# Main.net
KiCad netlist of a schematic drawn in Altium Designer
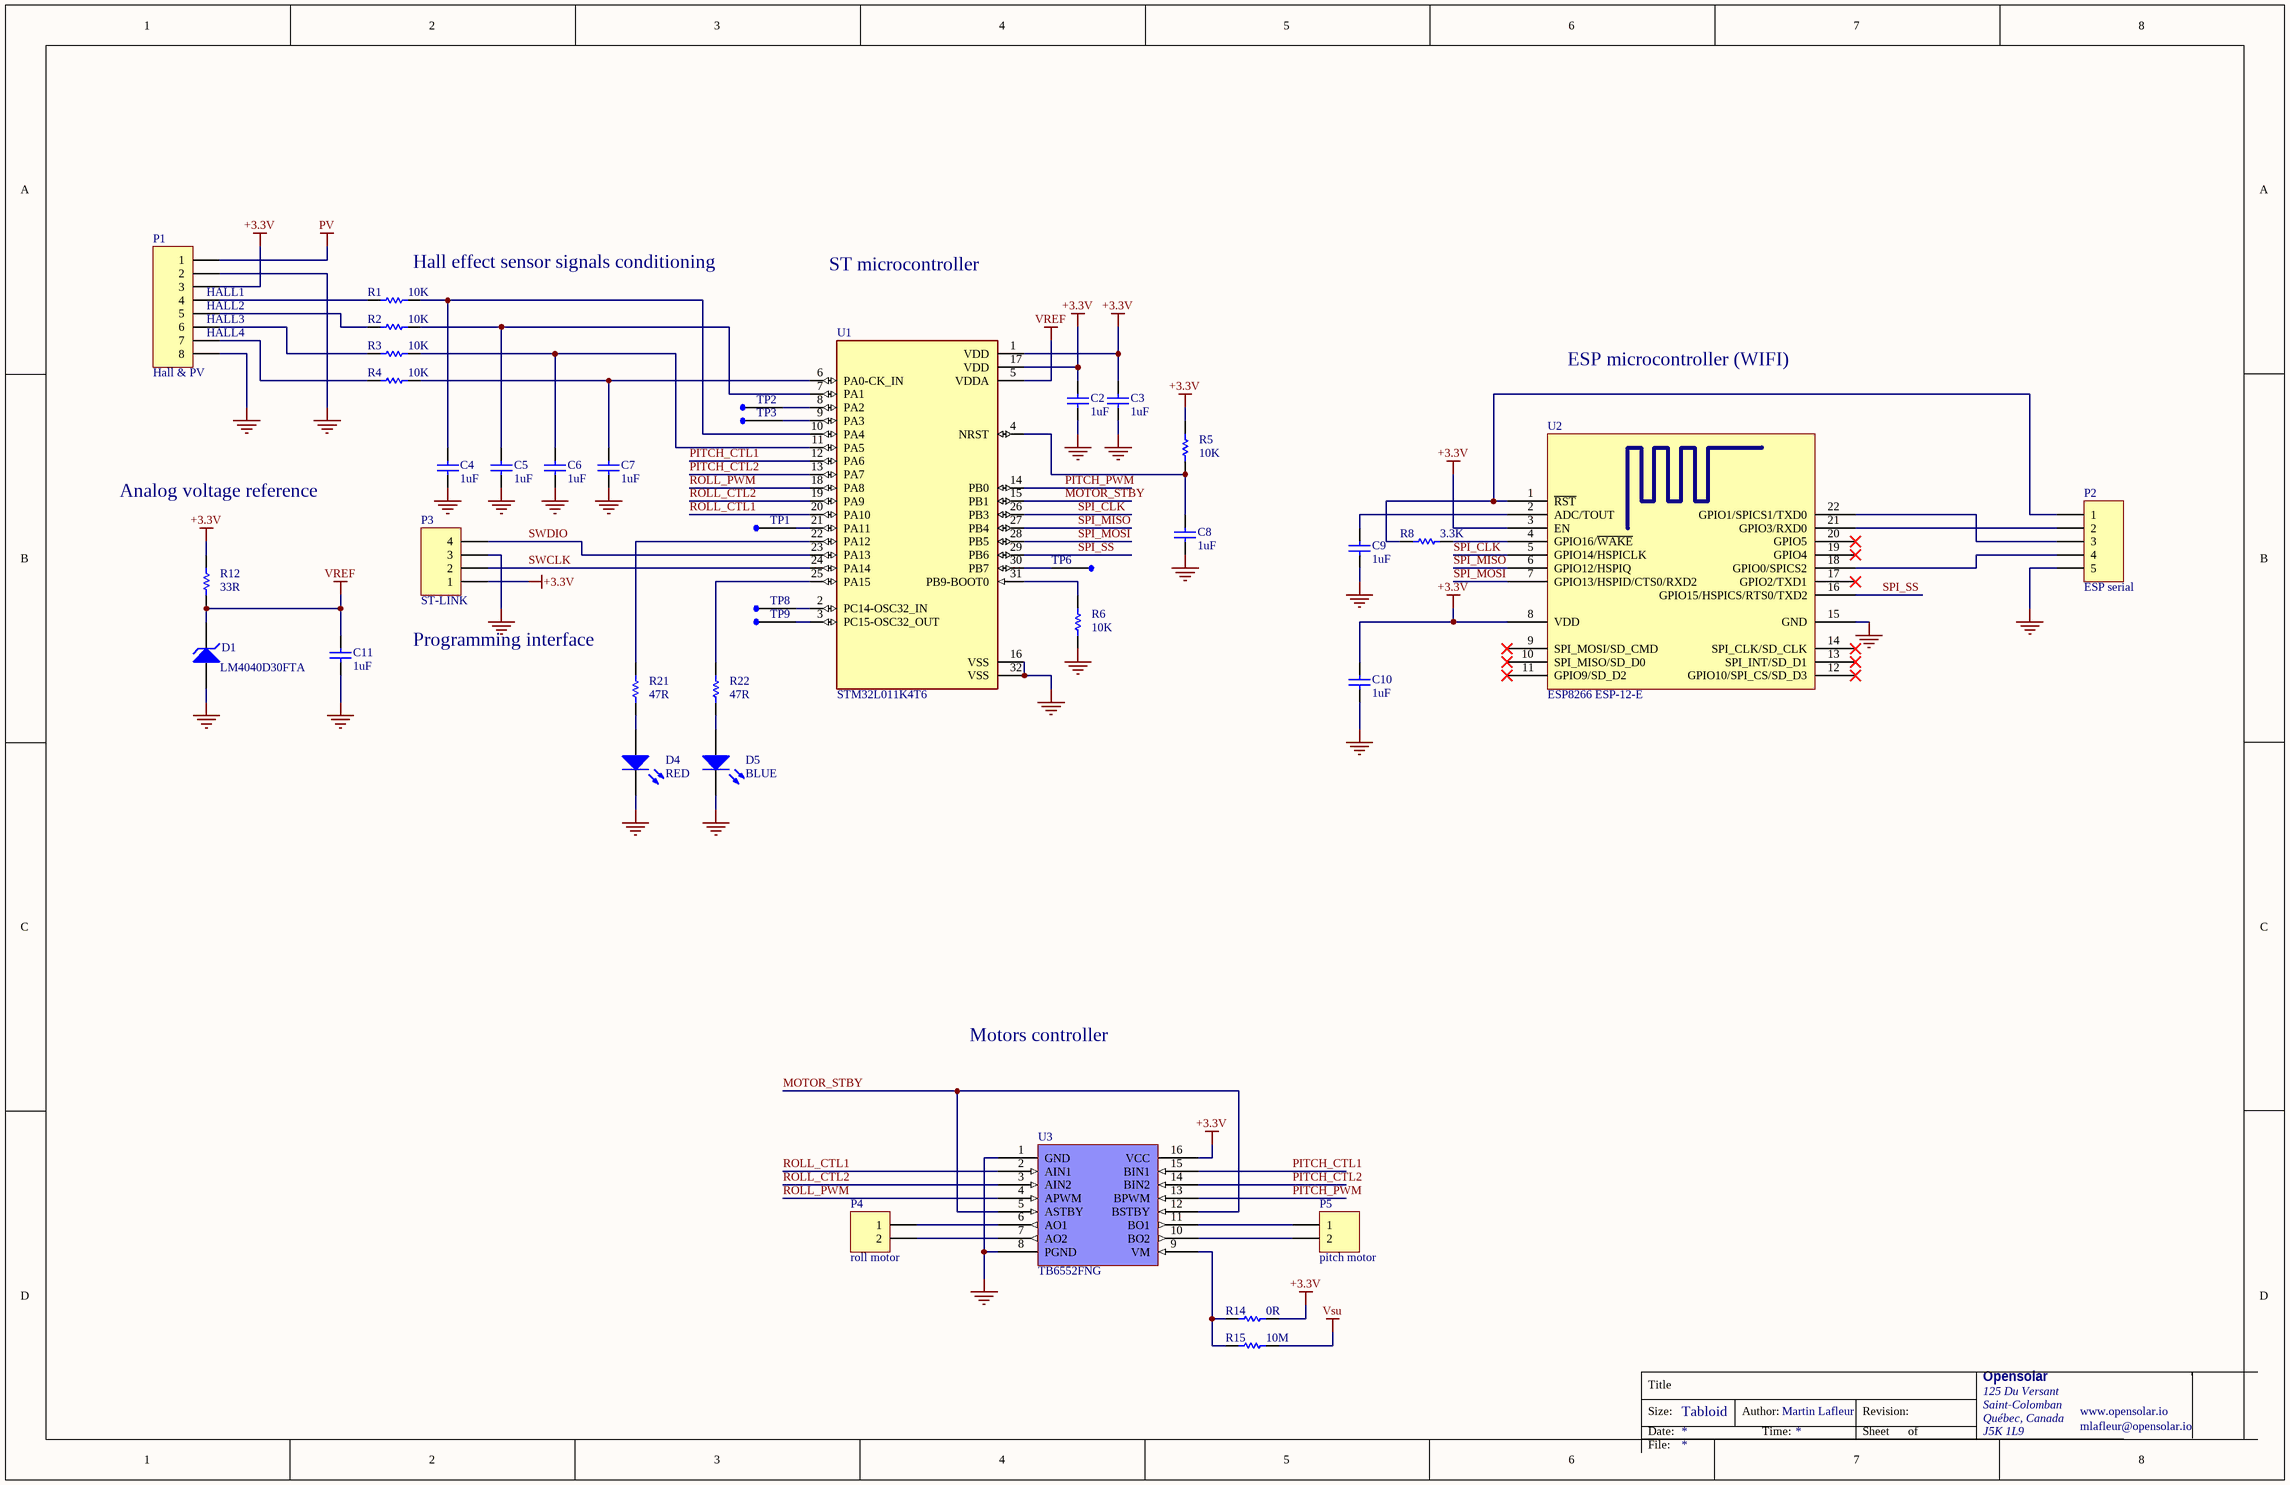
[diagram p0: Main.SchDoc]

(export (version "E")
  (design (tool "Eeschema 10.0.6"))
  (components
    (comp (ref "C2")
      (value "1uF")
      (footprint "6-0805_M")
      (description "Capacitor")
      (fields (field (name "PUBLISHER") "Altium Limited"))
      (libsource (lib "Miscellaneous Devices") (part "Cap"))
    )
    (comp (ref "C3")
      (value "1uF")
      (footprint "6-0805_M")
      (description "Capacitor")
      (fields (field (name "PUBLISHER") "Altium Limited"))
      (libsource (lib "Miscellaneous Devices") (part "Cap"))
    )
    (comp (ref "C4")
      (value "1uF")
      (footprint "6-0805_M")
      (description "Capacitor")
      (fields (field (name "PUBLISHER") "Altium Limited"))
      (libsource (lib "Miscellaneous Devices") (part "Cap"))
    )
    (comp (ref "C5")
      (value "1uF")
      (footprint "6-0805_M")
      (description "Capacitor")
      (fields (field (name "PUBLISHER") "Altium Limited"))
      (libsource (lib "Miscellaneous Devices") (part "Cap"))
    )
    (comp (ref "C6")
      (value "1uF")
      (footprint "6-0805_M")
      (description "Capacitor")
      (fields (field (name "PUBLISHER") "Altium Limited"))
      (libsource (lib "Miscellaneous Devices") (part "Cap"))
    )
    (comp (ref "C7")
      (value "1uF")
      (footprint "6-0805_M")
      (description "Capacitor")
      (fields (field (name "PUBLISHER") "Altium Limited"))
      (libsource (lib "Miscellaneous Devices") (part "Cap"))
    )
    (comp (ref "C8")
      (value "1uF")
      (footprint "6-0805_M")
      (description "Capacitor")
      (fields (field (name "PUBLISHER") "Altium Limited"))
      (libsource (lib "Miscellaneous Devices") (part "Cap"))
    )
    (comp (ref "C9")
      (value "1uF")
      (footprint "6-0805_M")
      (description "Capacitor")
      (fields (field (name "PUBLISHER") "Altium Limited"))
      (libsource (lib "Miscellaneous Devices") (part "Cap"))
    )
    (comp (ref "C10")
      (value "1uF")
      (footprint "6-0805_M")
      (description "Capacitor")
      (fields (field (name "PUBLISHER") "Altium Limited"))
      (libsource (lib "Miscellaneous Devices") (part "Cap"))
    )
    (comp (ref "C11")
      (value "1uF")
      (footprint "6-0805_M")
      (description "Capacitor")
      (fields (field (name "PUBLISHER") "Altium Limited"))
      (libsource (lib "Miscellaneous Devices") (part "Cap"))
    )
    (comp (ref "D1")
      (value "LM4040D30FTA")
      (footprint "SOT23_LM4040")
      (description "Zener Diode")
      (fields (field (name "PUBLISHER") "Altium Limited"))
      (libsource (lib "Miscellaneous Devices") (part "D Zener"))
    )
    (comp (ref "D4")
      (value "RED")
      (footprint "6-0805_M")
      (description "Typical RED, GREEN, YELLOW, AMBER GaAs LED")
      (fields (field (name "PUBLISHER") "Altium Limited"))
      (libsource (lib "Miscellaneous Devices") (part "LED2"))
    )
    (comp (ref "D5")
      (value "BLUE")
      (footprint "6-0805_M")
      (description "Typical RED, GREEN, YELLOW, AMBER GaAs LED")
      (fields (field (name "PUBLISHER") "Altium Limited"))
      (libsource (lib "Miscellaneous Devices") (part "LED2"))
    )
    (comp (ref "P1")
      (value "Hall & PV")
      (footprint "FFC_8")
      (description "Header, 8-Pin")
      (fields (field (name "PUBLISHER") "Altium Limited"))
      (libsource (lib "Miscellaneous Connectors") (part "Header 8"))
    )
    (comp (ref "P2")
      (value "ESP serial")
      (footprint "HEADER-1X5")
      (description "Header, 5-Pin")
      (fields (field (name "PUBLISHER") "Altium Limited"))
      (libsource (lib "Miscellaneous Connectors") (part "Header 5"))
    )
    (comp (ref "P3")
      (value "ST-LINK")
      (footprint "HEADER-1X4")
      (description "Header, 4-Pin")
      (fields (field (name "PUBLISHER") "Altium Limited"))
      (libsource (lib "Miscellaneous Connectors") (part "Header 4"))
    )
    (comp (ref "P4")
      (value "roll motor")
      (footprint "HEADER-1X2")
      (description "Header, 2-Pin")
      (fields (field (name "PUBLISHER") "Altium Limited"))
      (libsource (lib "Miscellaneous Connectors") (part "Header 2"))
    )
    (comp (ref "P5")
      (value "pitch motor")
      (footprint "HEADER-1X2")
      (description "Header, 2-Pin")
      (fields (field (name "PUBLISHER") "Altium Limited"))
      (libsource (lib "") (part "Header 2_1"))
    )
    (comp (ref "R1")
      (value "10K")
      (footprint "6-0805_N")
      (description "Resistor")
      (fields (field (name "PUBLISHER") "Altium Limited"))
      (libsource (lib "Miscellaneous Devices") (part "Res1"))
    )
    (comp (ref "R2")
      (value "10K")
      (footprint "6-0805_N")
      (description "Resistor")
      (fields (field (name "PUBLISHER") "Altium Limited"))
      (libsource (lib "Miscellaneous Devices") (part "Res1"))
    )
    (comp (ref "R3")
      (value "10K")
      (footprint "6-0805_N")
      (description "Resistor")
      (fields (field (name "PUBLISHER") "Altium Limited"))
      (libsource (lib "Miscellaneous Devices") (part "Res1"))
    )
    (comp (ref "R4")
      (value "10K")
      (footprint "6-0805_N")
      (description "Resistor")
      (fields (field (name "PUBLISHER") "Altium Limited"))
      (libsource (lib "Miscellaneous Devices") (part "Res1"))
    )
    (comp (ref "R5")
      (value "10K")
      (footprint "6-0805_N")
      (description "Resistor")
      (fields (field (name "PUBLISHER") "Altium Limited"))
      (libsource (lib "Miscellaneous Devices") (part "Res1"))
    )
    (comp (ref "R6")
      (value "10K")
      (footprint "6-0805_N")
      (description "Resistor")
      (fields (field (name "PUBLISHER") "Altium Limited"))
      (libsource (lib "Miscellaneous Devices") (part "Res1"))
    )
    (comp (ref "R8")
      (value "3.3K")
      (footprint "6-0805_N")
      (description "Resistor")
      (fields (field (name "PUBLISHER") "Altium Limited"))
      (libsource (lib "Miscellaneous Devices") (part "Res1"))
    )
    (comp (ref "R12")
      (value "33R")
      (footprint "6-0805_N")
      (description "Resistor")
      (fields (field (name "PUBLISHER") "Altium Limited"))
      (libsource (lib "Miscellaneous Devices") (part "Res1"))
    )
    (comp (ref "R14")
      (value "0R")
      (footprint "6-0805_N")
      (description "Resistor")
      (fields (field (name "PUBLISHER") "Altium Limited"))
      (libsource (lib "Miscellaneous Devices") (part "Res1"))
    )
    (comp (ref "R15")
      (value "10M")
      (footprint "6-0805_N")
      (description "Resistor")
      (fields (field (name "PUBLISHER") "Altium Limited"))
      (libsource (lib "Miscellaneous Devices") (part "Res1"))
    )
    (comp (ref "R21")
      (value "47R")
      (footprint "6-0805_N")
      (description "Resistor")
      (fields (field (name "PUBLISHER") "Altium Limited"))
      (libsource (lib "Miscellaneous Devices") (part "Res1"))
    )
    (comp (ref "R22")
      (value "47R")
      (footprint "6-0805_N")
      (description "Resistor")
      (fields (field (name "PUBLISHER") "Altium Limited"))
      (libsource (lib "Miscellaneous Devices") (part "Res1"))
    )
    (comp (ref "TP1")
      (value "TEST_POINT")
      (footprint "TEST_POINT_PAD")
      (libsource (lib "laf") (part "TEST_POINT"))
    )
    (comp (ref "TP2")
      (value "TEST_POINT")
      (footprint "TEST_POINT_PAD")
      (libsource (lib "laf") (part "TEST_POINT"))
    )
    (comp (ref "TP3")
      (value "TEST_POINT")
      (footprint "TEST_POINT_PAD")
      (libsource (lib "laf") (part "TEST_POINT"))
    )
    (comp (ref "TP6")
      (value "TEST_POINT")
      (footprint "TEST_POINT_PAD")
      (libsource (lib "laf") (part "TEST_POINT"))
    )
    (comp (ref "TP8")
      (value "TEST_POINT")
      (footprint "TEST_POINT_PAD")
      (libsource (lib "laf") (part "TEST_POINT"))
    )
    (comp (ref "TP9")
      (value "TEST_POINT")
      (footprint "TEST_POINT_PAD")
      (libsource (lib "laf") (part "TEST_POINT"))
    )
    (comp (ref "U1")
      (value "STM32L011K4T6")
      (footprint "QFP80P900X900X160-32N")
      (description "ARMÂ® CortexÂ®-M0 + STM32L0 Microcontrolador IC de 32 bits 32MHz 16KB _16K x 8_ FLASH 32-LQFP _7x7_")
      (fields (field (name "MF") "STMicroelectronics"))
      (libsource (lib "STM32L011K4T6") (part "STM32L011K4T6"))
    )
    (comp (ref "U2")
      (value "ESP8266 ESP-12-E")
      (footprint "ESP8266 ESP-12-E")
      (libsource (lib "ESP8266") (part "ESP8266 ESP-12-E"))
    )
    (comp (ref "U3")
      (value "TB6552FNG")
      (footprint "SSOP16_TB6652")
      (libsource (lib "laf") (part "TB6652PNG"))
    )
  )
  (nets
    (net (code "1") (name "+3.3V") (class "Default")
      (node (ref "C10") (pin "2") (pinfunction "2_2") (pintype "passive"))
      (node (ref "C2") (pin "2") (pinfunction "2_2") (pintype "passive"))
      (node (ref "C3") (pin "2") (pinfunction "2_2") (pintype "passive"))
      (node (ref "P1") (pin "3") (pinfunction "3_3") (pintype "passive"))
      (node (ref "P3") (pin "1") (pinfunction "1_1") (pintype "passive"))
      (node (ref "R12") (pin "2") (pinfunction "2_2") (pintype "passive"))
      (node (ref "R14") (pin "2") (pinfunction "2_2") (pintype "passive"))
      (node (ref "R5") (pin "1") (pinfunction "1_1") (pintype "passive"))
      (node (ref "U1") (pin "1") (pinfunction "VDD_1") (pintype "power_in"))
      (node (ref "U1") (pin "17") (pinfunction "VDD_17") (pintype "power_in"))
      (node (ref "U2") (pin "3") (pinfunction "EN_3") (pintype "passive"))
      (node (ref "U2") (pin "8") (pinfunction "VDD_8") (pintype "passive"))
      (node (ref "U3") (pin "16") (pinfunction "VCC_16") (pintype "power_in"))
    )
    (net (code "2") (name "/MOTOR_STBY") (class "Default")
      (node (ref "U1") (pin "15") (pinfunction "PB1_15") (pintype "bidirectional"))
      (node (ref "U3") (pin "12") (pinfunction "BSTBY_12") (pintype "input"))
      (node (ref "U3") (pin "5") (pinfunction "ASTBY_5") (pintype "input"))
    )
    (net (code "3") (name "/PITCH_CTL1") (class "Default")
      (node (ref "U1") (pin "12") (pinfunction "PA6_12") (pintype "bidirectional"))
      (node (ref "U3") (pin "15") (pinfunction "BIN1_15") (pintype "input"))
    )
    (net (code "4") (name "/PITCH_CTL2") (class "Default")
      (node (ref "U1") (pin "13") (pinfunction "PA7_13") (pintype "bidirectional"))
      (node (ref "U3") (pin "14") (pinfunction "BIN2_14") (pintype "input"))
    )
    (net (code "5") (name "/PITCH_PWM") (class "Default")
      (node (ref "U1") (pin "14") (pinfunction "PB0_14") (pintype "bidirectional"))
      (node (ref "U3") (pin "13") (pinfunction "BPWM_13") (pintype "input"))
    )
    (net (code "6") (name "/ROLL_CTL1") (class "Default")
      (node (ref "U1") (pin "20") (pinfunction "PA10_20") (pintype "bidirectional"))
      (node (ref "U3") (pin "2") (pinfunction "AIN1_2") (pintype "input"))
    )
    (net (code "7") (name "/ROLL_CTL2") (class "Default")
      (node (ref "U1") (pin "19") (pinfunction "PA9_19") (pintype "bidirectional"))
      (node (ref "U3") (pin "3") (pinfunction "AIN2_3") (pintype "input"))
    )
    (net (code "8") (name "/ROLL_PWM") (class "Default")
      (node (ref "U1") (pin "18") (pinfunction "PA8_18") (pintype "bidirectional"))
      (node (ref "U3") (pin "4") (pinfunction "APWM_4") (pintype "input"))
    )
    (net (code "9") (name "/SPI_CLK") (class "Default")
      (node (ref "U1") (pin "26") (pinfunction "PB3_26") (pintype "bidirectional"))
      (node (ref "U2") (pin "5") (pinfunction "GPIO14/HSPICLK_5") (pintype "passive"))
    )
    (net (code "10") (name "/SPI_MISO") (class "Default")
      (node (ref "U1") (pin "27") (pinfunction "PB4_27") (pintype "bidirectional"))
      (node (ref "U2") (pin "6") (pinfunction "GPIO12/HSPIQ_6") (pintype "passive"))
    )
    (net (code "11") (name "/SPI_MOSI") (class "Default")
      (node (ref "U1") (pin "28") (pinfunction "PB5_28") (pintype "bidirectional"))
      (node (ref "U2") (pin "7") (pinfunction "GPIO13/HSPID/CTS0/RXD2_7") (pintype "passive"))
    )
    (net (code "12") (name "/SPI_SS") (class "Default")
      (node (ref "U1") (pin "29") (pinfunction "PB6_29") (pintype "bidirectional"))
      (node (ref "U2") (pin "16") (pinfunction "GPIO15/HSPICS/RTS0/TXD2_16") (pintype "passive"))
    )
    (net (code "13") (name "/SWCLK") (class "Default")
      (node (ref "P3") (pin "2") (pinfunction "2_2") (pintype "passive"))
      (node (ref "U1") (pin "24") (pinfunction "PA14_24") (pintype "bidirectional"))
    )
    (net (code "14") (name "/SWDIO") (class "Default")
      (node (ref "P3") (pin "4") (pinfunction "4_4") (pintype "passive"))
      (node (ref "U1") (pin "23") (pinfunction "PA13_23") (pintype "bidirectional"))
    )
    (net (code "15") (name "GND") (class "Default")
      (node (ref "C10") (pin "1") (pinfunction "1_1") (pintype "passive"))
      (node (ref "C11") (pin "1") (pinfunction "1_1") (pintype "passive"))
      (node (ref "C2") (pin "1") (pinfunction "1_1") (pintype "passive"))
      (node (ref "C3") (pin "1") (pinfunction "1_1") (pintype "passive"))
      (node (ref "C4") (pin "1") (pinfunction "1_1") (pintype "passive"))
      (node (ref "C5") (pin "1") (pinfunction "1_1") (pintype "passive"))
      (node (ref "C6") (pin "1") (pinfunction "1_1") (pintype "passive"))
      (node (ref "C7") (pin "1") (pinfunction "1_1") (pintype "passive"))
      (node (ref "C8") (pin "1") (pinfunction "1_1") (pintype "passive"))
      (node (ref "C9") (pin "1") (pinfunction "1_1") (pintype "passive"))
      (node (ref "D1") (pin "1") (pinfunction "A_1") (pintype "passive"))
      (node (ref "D4") (pin "2") (pinfunction "K_2") (pintype "passive"))
      (node (ref "D5") (pin "2") (pinfunction "K_2") (pintype "passive"))
      (node (ref "P1") (pin "2") (pinfunction "2_2") (pintype "passive"))
      (node (ref "P1") (pin "8") (pinfunction "8_8") (pintype "passive"))
      (node (ref "P2") (pin "5") (pinfunction "5_5") (pintype "passive"))
      (node (ref "P3") (pin "3") (pinfunction "3_3") (pintype "passive"))
      (node (ref "R6") (pin "1") (pinfunction "1_1") (pintype "passive"))
      (node (ref "U1") (pin "16") (pinfunction "VSS_16") (pintype "power_in"))
      (node (ref "U1") (pin "32") (pinfunction "VSS_32") (pintype "power_in"))
      (node (ref "U2") (pin "15") (pinfunction "GND_15") (pintype "passive"))
      (node (ref "U3") (pin "1") (pinfunction "GND_1") (pintype "power_in"))
      (node (ref "U3") (pin "8") (pinfunction "PGND_8") (pintype "power_in"))
    )
    (net (code "16") (name "Net-(D4-A)") (class "Default")
      (node (ref "D4") (pin "1") (pinfunction "A_1") (pintype "passive"))
      (node (ref "R21") (pin "1") (pinfunction "1_1") (pintype "passive"))
    )
    (net (code "17") (name "Net-(D5-A)") (class "Default")
      (node (ref "D5") (pin "1") (pinfunction "A_1") (pintype "passive"))
      (node (ref "R22") (pin "1") (pinfunction "1_1") (pintype "passive"))
    )
    (net (code "18") (name "Net-(P1-Pad4)") (class "Default")
      (node (ref "P1") (pin "4") (pinfunction "4_4") (pintype "passive"))
      (node (ref "R1") (pin "2") (pinfunction "2_2") (pintype "passive"))
    )
    (net (code "19") (name "Net-(P1-Pad5)") (class "Default")
      (node (ref "P1") (pin "5") (pinfunction "5_5") (pintype "passive"))
      (node (ref "R2") (pin "2") (pinfunction "2_2") (pintype "passive"))
    )
    (net (code "20") (name "Net-(P1-Pad6)") (class "Default")
      (node (ref "P1") (pin "6") (pinfunction "6_6") (pintype "passive"))
      (node (ref "R3") (pin "2") (pinfunction "2_2") (pintype "passive"))
    )
    (net (code "21") (name "Net-(P1-Pad7)") (class "Default")
      (node (ref "P1") (pin "7") (pinfunction "7_7") (pintype "passive"))
      (node (ref "R4") (pin "2") (pinfunction "2_2") (pintype "passive"))
    )
    (net (code "22") (name "Net-(TP1-0)") (class "Default")
      (node (ref "TP1") (pin "1") (pinfunction "0_1") (pintype "passive"))
      (node (ref "U1") (pin "21") (pinfunction "PA11_21") (pintype "bidirectional"))
    )
    (net (code "23") (name "Net-(TP2-0)") (class "Default")
      (node (ref "TP2") (pin "1") (pinfunction "0_1") (pintype "passive"))
      (node (ref "U1") (pin "8") (pinfunction "PA2_8") (pintype "bidirectional"))
    )
    (net (code "24") (name "Net-(TP3-0)") (class "Default")
      (node (ref "TP3") (pin "1") (pinfunction "0_1") (pintype "passive"))
      (node (ref "U1") (pin "9") (pinfunction "PA3_9") (pintype "bidirectional"))
    )
    (net (code "25") (name "Net-(TP6-0)") (class "Default")
      (node (ref "TP6") (pin "1") (pinfunction "0_1") (pintype "passive"))
      (node (ref "U1") (pin "30") (pinfunction "PB7_30") (pintype "bidirectional"))
    )
    (net (code "26") (name "Net-(TP8-0)") (class "Default")
      (node (ref "TP8") (pin "1") (pinfunction "0_1") (pintype "passive"))
      (node (ref "U1") (pin "2") (pinfunction "PC14-OSC32_IN_2") (pintype "bidirectional"))
    )
    (net (code "27") (name "Net-(TP9-0)") (class "Default")
      (node (ref "TP9") (pin "1") (pinfunction "0_1") (pintype "passive"))
      (node (ref "U1") (pin "3") (pinfunction "PC15-OSC32_OUT_3") (pintype "bidirectional"))
    )
    (net (code "28") (name "Net-(U1-NRST)") (class "Default")
      (node (ref "C8") (pin "2") (pinfunction "2_2") (pintype "passive"))
      (node (ref "R5") (pin "2") (pinfunction "2_2") (pintype "passive"))
      (node (ref "U1") (pin "4") (pinfunction "NRST_4") (pintype "bidirectional"))
    )
    (net (code "29") (name "Net-(U1-PA0-CK_IN)") (class "Default")
      (node (ref "C7") (pin "2") (pinfunction "2_2") (pintype "passive"))
      (node (ref "R4") (pin "1") (pinfunction "1_1") (pintype "passive"))
      (node (ref "U1") (pin "6") (pinfunction "PA0-CK_IN_6") (pintype "bidirectional"))
    )
    (net (code "30") (name "Net-(U1-PA1)") (class "Default")
      (node (ref "C5") (pin "2") (pinfunction "2_2") (pintype "passive"))
      (node (ref "R2") (pin "1") (pinfunction "1_1") (pintype "passive"))
      (node (ref "U1") (pin "7") (pinfunction "PA1_7") (pintype "bidirectional"))
    )
    (net (code "31") (name "Net-(U1-PA4)") (class "Default")
      (node (ref "C4") (pin "2") (pinfunction "2_2") (pintype "passive"))
      (node (ref "R1") (pin "1") (pinfunction "1_1") (pintype "passive"))
      (node (ref "U1") (pin "10") (pinfunction "PA4_10") (pintype "bidirectional"))
    )
    (net (code "32") (name "Net-(U1-PA5)") (class "Default")
      (node (ref "C6") (pin "2") (pinfunction "2_2") (pintype "passive"))
      (node (ref "R3") (pin "1") (pinfunction "1_1") (pintype "passive"))
      (node (ref "U1") (pin "11") (pinfunction "PA5_11") (pintype "bidirectional"))
    )
    (net (code "33") (name "Net-(U1-PA12)") (class "Default")
      (node (ref "R21") (pin "2") (pinfunction "2_2") (pintype "passive"))
      (node (ref "U1") (pin "22") (pinfunction "PA12_22") (pintype "bidirectional"))
    )
    (net (code "34") (name "Net-(U1-PA15)") (class "Default")
      (node (ref "R22") (pin "2") (pinfunction "2_2") (pintype "passive"))
      (node (ref "U1") (pin "25") (pinfunction "PA15_25") (pintype "bidirectional"))
    )
    (net (code "35") (name "Net-(U1-PB9-BOOT0)") (class "Default")
      (node (ref "R6") (pin "2") (pinfunction "2_2") (pintype "passive"))
      (node (ref "U1") (pin "31") (pinfunction "PB9-BOOT0_31") (pintype "input"))
    )
    (net (code "36") (name "Net-(U2-ADC{slash}TOUT)") (class "Default")
      (node (ref "C9") (pin "2") (pinfunction "2_2") (pintype "passive"))
      (node (ref "U2") (pin "2") (pinfunction "ADC/TOUT_2") (pintype "passive"))
    )
    (net (code "37") (name "Net-(U2-GPIO0{slash}SPICS2)") (class "Default")
      (node (ref "P2") (pin "4") (pinfunction "4_4") (pintype "passive"))
      (node (ref "U2") (pin "18") (pinfunction "GPIO0/SPICS2_18") (pintype "passive"))
    )
    (net (code "38") (name "Net-(U2-GPIO1{slash}SPICS1{slash}TXD0)") (class "Default")
      (node (ref "P2") (pin "3") (pinfunction "3_3") (pintype "passive"))
      (node (ref "U2") (pin "22") (pinfunction "GPIO1/SPICS1/TXD0_22") (pintype "passive"))
    )
    (net (code "39") (name "Net-(U2-GPIO3{slash}RXD0)") (class "Default")
      (node (ref "P2") (pin "2") (pinfunction "2_2") (pintype "passive"))
      (node (ref "U2") (pin "21") (pinfunction "GPIO3/RXD0_21") (pintype "passive"))
    )
    (net (code "40") (name "Net-(U2-GPIO16{slash}~{WAKE})") (class "Default")
      (node (ref "R8") (pin "2") (pinfunction "2_2") (pintype "passive"))
      (node (ref "U2") (pin "4") (pinfunction "GPIO16/~{WAKE}_4") (pintype "passive"))
    )
    (net (code "41") (name "Net-(U2-~{RST})") (class "Default")
      (node (ref "P2") (pin "1") (pinfunction "1_1") (pintype "passive"))
      (node (ref "R8") (pin "1") (pinfunction "1_1") (pintype "passive"))
      (node (ref "U2") (pin "1") (pinfunction "~{RST}_1") (pintype "passive"))
    )
    (net (code "42") (name "Net-(U3-AO1)") (class "Default")
      (node (ref "P4") (pin "1") (pinfunction "1_1") (pintype "passive"))
      (node (ref "U3") (pin "6") (pinfunction "AO1_6") (pintype "output"))
    )
    (net (code "43") (name "Net-(U3-AO2)") (class "Default")
      (node (ref "P4") (pin "2") (pinfunction "2_2") (pintype "passive"))
      (node (ref "U3") (pin "7") (pinfunction "AO2_7") (pintype "output"))
    )
    (net (code "44") (name "Net-(U3-BO1)") (class "Default")
      (node (ref "P5") (pin "1") (pinfunction "1_1") (pintype "passive"))
      (node (ref "U3") (pin "11") (pinfunction "BO1_11") (pintype "output"))
    )
    (net (code "45") (name "Net-(U3-BO2)") (class "Default")
      (node (ref "P5") (pin "2") (pinfunction "2_2") (pintype "passive"))
      (node (ref "U3") (pin "10") (pinfunction "BO2_10") (pintype "output"))
    )
    (net (code "46") (name "Net-(U3-VM)") (class "Default")
      (node (ref "R14") (pin "1") (pinfunction "1_1") (pintype "passive"))
      (node (ref "R15") (pin "1") (pinfunction "1_1") (pintype "passive"))
      (node (ref "U3") (pin "9") (pinfunction "VM_9") (pintype "input"))
    )
    (net (code "47") (name "PV") (class "Default")
      (node (ref "P1") (pin "1") (pinfunction "1_1") (pintype "passive"))
    )
    (net (code "48") (name "VREF") (class "Default")
      (node (ref "C11") (pin "2") (pinfunction "2_2") (pintype "passive"))
      (node (ref "D1") (pin "2") (pinfunction "K_2") (pintype "passive"))
      (node (ref "R12") (pin "1") (pinfunction "1_1") (pintype "passive"))
      (node (ref "U1") (pin "5") (pinfunction "VDDA_5") (pintype "power_in"))
    )
    (net (code "49") (name "Vsu") (class "Default")
      (node (ref "R15") (pin "2") (pinfunction "2_2") (pintype "passive"))
    )
    (net (code "50") (name "unconnected-(U2-GPIO2{slash}TXD1-Pad17)") (class "Default")
      (node (ref "U2") (pin "17") (pinfunction "GPIO2/TXD1_17") (pintype "passive+no_connect"))
    )
    (net (code "51") (name "unconnected-(U2-GPIO4-Pad19)") (class "Default")
      (node (ref "U2") (pin "19") (pinfunction "GPIO4_19") (pintype "passive+no_connect"))
    )
    (net (code "52") (name "unconnected-(U2-GPIO5-Pad20)") (class "Default")
      (node (ref "U2") (pin "20") (pinfunction "GPIO5_20") (pintype "passive+no_connect"))
    )
    (net (code "53") (name "unconnected-(U2-GPIO9{slash}SD_D2-Pad11)") (class "Default")
      (node (ref "U2") (pin "11") (pinfunction "GPIO9/SD_D2_11") (pintype "passive+no_connect"))
    )
    (net (code "54") (name "unconnected-(U2-GPIO10{slash}SPI_CS{slash}SD_D3-Pad12)") (class "Default")
      (node (ref "U2") (pin "12") (pinfunction "GPIO10/SPI_CS/SD_D3_12") (pintype "passive+no_connect"))
    )
    (net (code "55") (name "unconnected-(U2-SPI_CLK{slash}SD_CLK-Pad14)") (class "Default")
      (node (ref "U2") (pin "14") (pinfunction "SPI_CLK/SD_CLK_14") (pintype "passive+no_connect"))
    )
    (net (code "56") (name "unconnected-(U2-SPI_INT{slash}SD_D1-Pad13)") (class "Default")
      (node (ref "U2") (pin "13") (pinfunction "SPI_INT/SD_D1_13") (pintype "passive+no_connect"))
    )
    (net (code "57") (name "unconnected-(U2-SPI_MISO{slash}SD_D0-Pad10)") (class "Default")
      (node (ref "U2") (pin "10") (pinfunction "SPI_MISO/SD_D0_10") (pintype "passive+no_connect"))
    )
    (net (code "58") (name "unconnected-(U2-SPI_MOSI{slash}SD_CMD-Pad9)") (class "Default")
      (node (ref "U2") (pin "9") (pinfunction "SPI_MOSI/SD_CMD_9") (pintype "passive+no_connect"))
    )
  )
)
